# sonar_direction.net
KiCad netlist of a schematic drawn in EAGLE
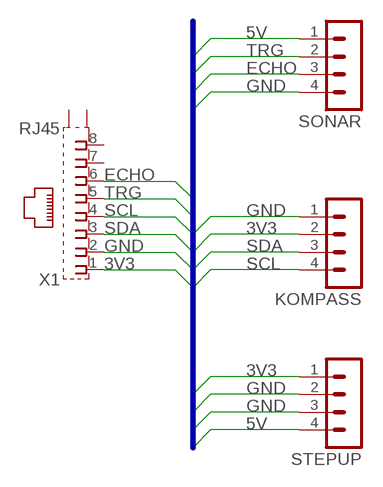
[diagram p0: schematic, sheet 1]

(export (version "E")
  (design (tool "Eeschema 10.0.6"))
  (components
    (comp (ref "KOMPASS")
      (value "MA04-1")
      (footprint "eagle-import:MA04-1")
      (libsource (lib "eagle-import") (part "MA04-1"))
    )
    (comp (ref "SONAR")
      (value "MA04-1")
      (footprint "eagle-import:MA04-1")
      (libsource (lib "eagle-import") (part "MA04-1"))
    )
    (comp (ref "STEPUP")
      (value "MA04-1")
      (footprint "eagle-import:MA04-1")
      (libsource (lib "eagle-import") (part "MA04-1"))
    )
    (comp (ref "X1")
      (value "RJ45")
      (footprint "eagle-import:GLX-S-88M")
      (libsource (lib "eagle-import") (part "GLX-S-88M"))
    )
  )
  (nets
    (net (code "1") (name "/3V3") (class "Default")
      (node (ref "KOMPASS") (pin "2") (pinfunction "2_2") (pintype "passive"))
      (node (ref "STEPUP") (pin "1") (pinfunction "1_1") (pintype "passive"))
      (node (ref "X1") (pin "1") (pinfunction "1_1") (pintype "passive"))
    )
    (net (code "2") (name "/5V") (class "Default")
      (node (ref "SONAR") (pin "1") (pinfunction "1_1") (pintype "passive"))
      (node (ref "STEPUP") (pin "4") (pinfunction "4_4") (pintype "passive"))
    )
    (net (code "3") (name "/ECHO") (class "Default")
      (node (ref "SONAR") (pin "3") (pinfunction "3_3") (pintype "passive"))
      (node (ref "X1") (pin "6") (pinfunction "6_6") (pintype "passive"))
    )
    (net (code "4") (name "/GND") (class "Default")
      (node (ref "KOMPASS") (pin "1") (pinfunction "1_1") (pintype "passive"))
      (node (ref "SONAR") (pin "4") (pinfunction "4_4") (pintype "passive"))
      (node (ref "STEPUP") (pin "2") (pinfunction "2_2") (pintype "passive"))
      (node (ref "STEPUP") (pin "3") (pinfunction "3_3") (pintype "passive"))
      (node (ref "X1") (pin "2") (pinfunction "2_2") (pintype "passive"))
    )
    (net (code "5") (name "/SCL") (class "Default")
      (node (ref "KOMPASS") (pin "4") (pinfunction "4_4") (pintype "passive"))
      (node (ref "X1") (pin "4") (pinfunction "4_4") (pintype "passive"))
    )
    (net (code "6") (name "/SDA") (class "Default")
      (node (ref "KOMPASS") (pin "3") (pinfunction "3_3") (pintype "passive"))
      (node (ref "X1") (pin "3") (pinfunction "3_3") (pintype "passive"))
    )
    (net (code "7") (name "/TRG") (class "Default")
      (node (ref "SONAR") (pin "2") (pinfunction "2_2") (pintype "passive"))
      (node (ref "X1") (pin "5") (pinfunction "5_5") (pintype "passive"))
    )
    (net (code "8") (name "unconnected-(X1-Pad7)") (class "Default")
      (node (ref "X1") (pin "7") (pinfunction "7_7") (pintype "passive"))
    )
    (net (code "9") (name "unconnected-(X1-Pad8)") (class "Default")
      (node (ref "X1") (pin "8") (pinfunction "8_8") (pintype "passive"))
    )
    (net (code "10") (name "unconnected-(X1-PadS1)") (class "Default")
      (node (ref "X1") (pin "S1") (pinfunction "S1_S1") (pintype "passive"))
    )
    (net (code "11") (name "unconnected-(X1-PadS2)") (class "Default")
      (node (ref "X1") (pin "S2") (pinfunction "S2_S2") (pintype "passive"))
    )
  )
)
